# FPGA_Board_Input_Signals.net
KiCad netlist of a schematic drawn in Altium Designer
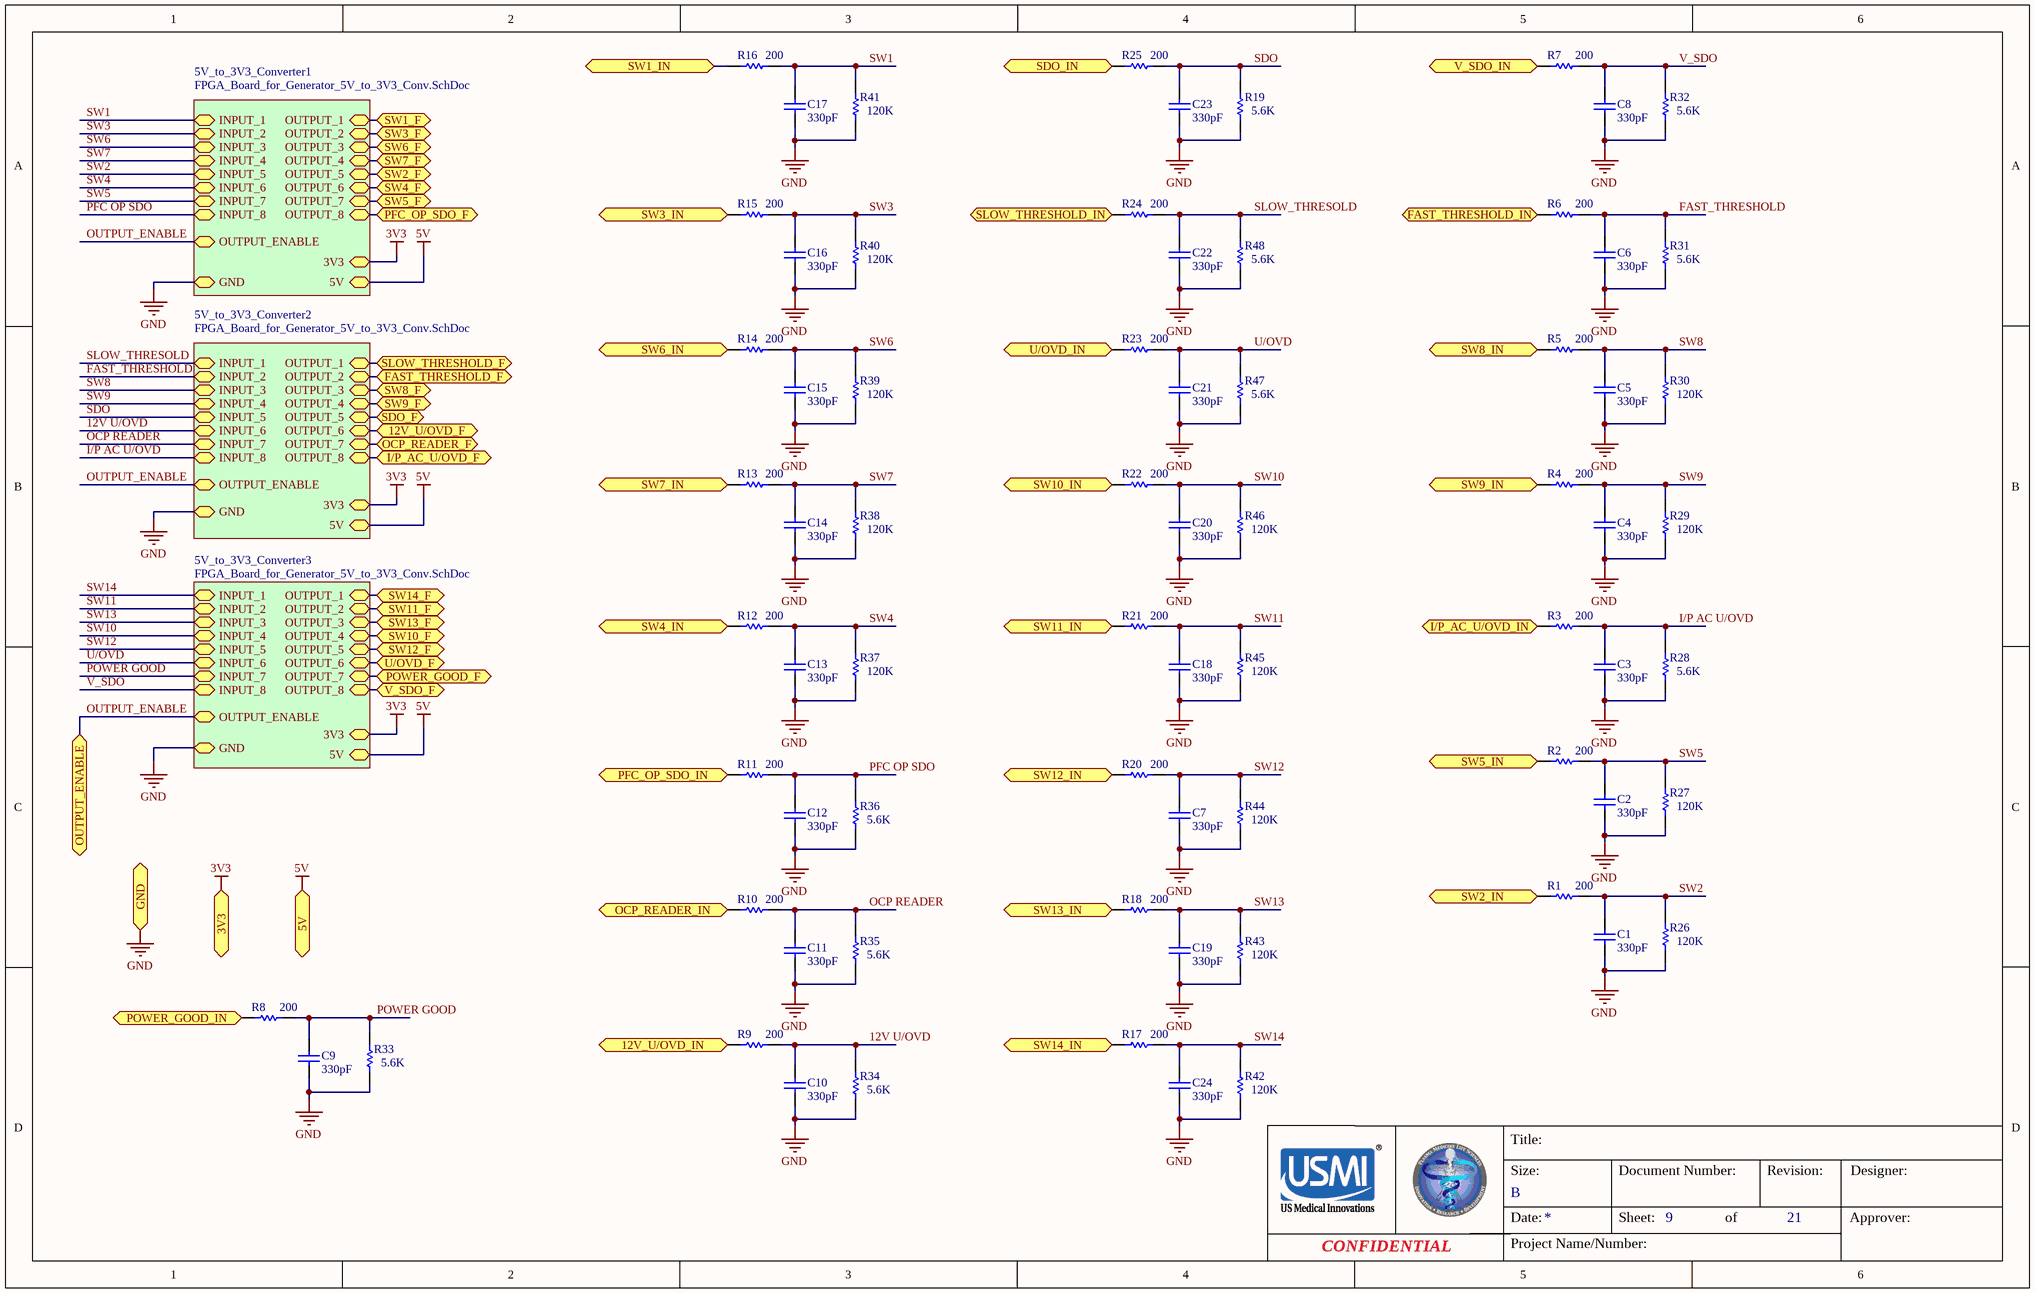
[diagram p0: FPGA_Board_Input_Signals.SchDoc]

(export (version "E")
  (design (tool "Eeschema 10.0.6"))
  (components
    (comp (ref "C1")
      (value "330pF")
      (footprint "0603c")
      (description "Capacitor")
      (fields (field (name "PUBLISHER") "Altium Limited"))
      (libsource (lib "Buddika Miscellaneous Devices") (part "Cap"))
    )
    (comp (ref "C2")
      (value "330pF")
      (footprint "0603c")
      (description "Capacitor")
      (fields (field (name "PUBLISHER") "Altium Limited"))
      (libsource (lib "Buddika Miscellaneous Devices") (part "Cap"))
    )
    (comp (ref "C3")
      (value "330pF")
      (footprint "0603c")
      (description "Capacitor")
      (fields (field (name "PUBLISHER") "Altium Limited"))
      (libsource (lib "Buddika Miscellaneous Devices") (part "Cap"))
    )
    (comp (ref "C4")
      (value "330pF")
      (footprint "0603c")
      (description "Capacitor")
      (fields (field (name "PUBLISHER") "Altium Limited"))
      (libsource (lib "Buddika Miscellaneous Devices") (part "Cap"))
    )
    (comp (ref "C5")
      (value "330pF")
      (footprint "0603c")
      (description "Capacitor")
      (fields (field (name "PUBLISHER") "Altium Limited"))
      (libsource (lib "Buddika Miscellaneous Devices") (part "Cap"))
    )
    (comp (ref "C6")
      (value "330pF")
      (footprint "0603c")
      (description "Capacitor")
      (fields (field (name "PUBLISHER") "Altium Limited"))
      (libsource (lib "Buddika Miscellaneous Devices") (part "Cap"))
    )
    (comp (ref "C7")
      (value "330pF")
      (footprint "0603c")
      (description "Capacitor")
      (fields (field (name "PUBLISHER") "Altium Limited"))
      (libsource (lib "Buddika Miscellaneous Devices") (part "Cap"))
    )
    (comp (ref "C8")
      (value "330pF")
      (footprint "0603c")
      (description "Capacitor")
      (fields (field (name "PUBLISHER") "Altium Limited"))
      (libsource (lib "Buddika Miscellaneous Devices") (part "Cap"))
    )
    (comp (ref "C9")
      (value "330pF")
      (footprint "0603c")
      (description "Capacitor")
      (fields (field (name "PUBLISHER") "Altium Limited"))
      (libsource (lib "Buddika Miscellaneous Devices") (part "Cap"))
    )
    (comp (ref "C10")
      (value "330pF")
      (footprint "0603c")
      (description "Capacitor")
      (fields (field (name "PUBLISHER") "Altium Limited"))
      (libsource (lib "Buddika Miscellaneous Devices") (part "Cap"))
    )
    (comp (ref "C11")
      (value "330pF")
      (footprint "0603c")
      (description "Capacitor")
      (fields (field (name "PUBLISHER") "Altium Limited"))
      (libsource (lib "Buddika Miscellaneous Devices") (part "Cap"))
    )
    (comp (ref "C12")
      (value "330pF")
      (footprint "0603c")
      (description "Capacitor")
      (fields (field (name "PUBLISHER") "Altium Limited"))
      (libsource (lib "Buddika Miscellaneous Devices") (part "Cap"))
    )
    (comp (ref "C13")
      (value "330pF")
      (footprint "0603c")
      (description "Capacitor")
      (fields (field (name "PUBLISHER") "Altium Limited"))
      (libsource (lib "Buddika Miscellaneous Devices") (part "Cap"))
    )
    (comp (ref "C14")
      (value "330pF")
      (footprint "0603c")
      (description "Capacitor")
      (fields (field (name "PUBLISHER") "Altium Limited"))
      (libsource (lib "Buddika Miscellaneous Devices") (part "Cap"))
    )
    (comp (ref "C15")
      (value "330pF")
      (footprint "0603c")
      (description "Capacitor")
      (fields (field (name "PUBLISHER") "Altium Limited"))
      (libsource (lib "Buddika Miscellaneous Devices") (part "Cap"))
    )
    (comp (ref "C16")
      (value "330pF")
      (footprint "0603c")
      (description "Capacitor")
      (fields (field (name "PUBLISHER") "Altium Limited"))
      (libsource (lib "Buddika Miscellaneous Devices") (part "Cap"))
    )
    (comp (ref "C17")
      (value "330pF")
      (footprint "0603c")
      (description "Capacitor")
      (fields (field (name "PUBLISHER") "Altium Limited"))
      (libsource (lib "Buddika Miscellaneous Devices") (part "Cap"))
    )
    (comp (ref "C18")
      (value "330pF")
      (footprint "0603c")
      (description "Capacitor")
      (fields (field (name "PUBLISHER") "Altium Limited"))
      (libsource (lib "Buddika Miscellaneous Devices") (part "Cap"))
    )
    (comp (ref "C19")
      (value "330pF")
      (footprint "0603c")
      (description "Capacitor")
      (fields (field (name "PUBLISHER") "Altium Limited"))
      (libsource (lib "Buddika Miscellaneous Devices") (part "Cap"))
    )
    (comp (ref "C20")
      (value "330pF")
      (footprint "0603c")
      (description "Capacitor")
      (fields (field (name "PUBLISHER") "Altium Limited"))
      (libsource (lib "Buddika Miscellaneous Devices") (part "Cap"))
    )
    (comp (ref "C21")
      (value "330pF")
      (footprint "0603c")
      (description "Capacitor")
      (fields (field (name "PUBLISHER") "Altium Limited"))
      (libsource (lib "Buddika Miscellaneous Devices") (part "Cap"))
    )
    (comp (ref "C22")
      (value "330pF")
      (footprint "0603c")
      (description "Capacitor")
      (fields (field (name "PUBLISHER") "Altium Limited"))
      (libsource (lib "Buddika Miscellaneous Devices") (part "Cap"))
    )
    (comp (ref "C23")
      (value "330pF")
      (footprint "0603c")
      (description "Capacitor")
      (fields (field (name "PUBLISHER") "Altium Limited"))
      (libsource (lib "Buddika Miscellaneous Devices") (part "Cap"))
    )
    (comp (ref "C24")
      (value "330pF")
      (footprint "0603c")
      (description "Capacitor")
      (fields (field (name "PUBLISHER") "Altium Limited"))
      (libsource (lib "Buddika Miscellaneous Devices") (part "Cap"))
    )
    (comp (ref "R1")
      (value "200")
      (footprint "0603R")
      (description "Resistor")
      (fields (field (name "PUBLISHER") "Altium Limited"))
      (libsource (lib "Buddika Miscellaneous Devices") (part "Res1"))
    )
    (comp (ref "R2")
      (value "200")
      (footprint "0603R")
      (description "Resistor")
      (fields (field (name "PUBLISHER") "Altium Limited"))
      (libsource (lib "Buddika Miscellaneous Devices") (part "Res1"))
    )
    (comp (ref "R3")
      (value "200")
      (footprint "0603R")
      (description "Resistor")
      (fields (field (name "PUBLISHER") "Altium Limited"))
      (libsource (lib "Buddika Miscellaneous Devices") (part "Res1"))
    )
    (comp (ref "R4")
      (value "200")
      (footprint "0603R")
      (description "Resistor")
      (fields (field (name "PUBLISHER") "Altium Limited"))
      (libsource (lib "Buddika Miscellaneous Devices") (part "Res1"))
    )
    (comp (ref "R5")
      (value "200")
      (footprint "0603R")
      (description "Resistor")
      (fields (field (name "PUBLISHER") "Altium Limited"))
      (libsource (lib "Buddika Miscellaneous Devices") (part "Res1"))
    )
    (comp (ref "R6")
      (value "200")
      (footprint "0603R")
      (description "Resistor")
      (fields (field (name "PUBLISHER") "Altium Limited"))
      (libsource (lib "Buddika Miscellaneous Devices") (part "Res1"))
    )
    (comp (ref "R7")
      (value "200")
      (footprint "0603R")
      (description "Resistor")
      (fields (field (name "PUBLISHER") "Altium Limited"))
      (libsource (lib "Buddika Miscellaneous Devices") (part "Res1"))
    )
    (comp (ref "R8")
      (value "200")
      (footprint "0603R")
      (description "Resistor")
      (fields (field (name "PUBLISHER") "Altium Limited"))
      (libsource (lib "Buddika Miscellaneous Devices") (part "Res1"))
    )
    (comp (ref "R9")
      (value "200")
      (footprint "0603R")
      (description "Resistor")
      (fields (field (name "PUBLISHER") "Altium Limited"))
      (libsource (lib "Buddika Miscellaneous Devices") (part "Res1"))
    )
    (comp (ref "R10")
      (value "200")
      (footprint "0603R")
      (description "Resistor")
      (fields (field (name "PUBLISHER") "Altium Limited"))
      (libsource (lib "Buddika Miscellaneous Devices") (part "Res1"))
    )
    (comp (ref "R11")
      (value "200")
      (footprint "0603R")
      (description "Resistor")
      (fields (field (name "PUBLISHER") "Altium Limited"))
      (libsource (lib "Buddika Miscellaneous Devices") (part "Res1"))
    )
    (comp (ref "R12")
      (value "200")
      (footprint "0603R")
      (description "Resistor")
      (fields (field (name "PUBLISHER") "Altium Limited"))
      (libsource (lib "Buddika Miscellaneous Devices") (part "Res1"))
    )
    (comp (ref "R13")
      (value "200")
      (footprint "0603R")
      (description "Resistor")
      (fields (field (name "PUBLISHER") "Altium Limited"))
      (libsource (lib "Buddika Miscellaneous Devices") (part "Res1"))
    )
    (comp (ref "R14")
      (value "200")
      (footprint "0603R")
      (description "Resistor")
      (fields (field (name "PUBLISHER") "Altium Limited"))
      (libsource (lib "Buddika Miscellaneous Devices") (part "Res1"))
    )
    (comp (ref "R15")
      (value "200")
      (footprint "0603R")
      (description "Resistor")
      (fields (field (name "PUBLISHER") "Altium Limited"))
      (libsource (lib "Buddika Miscellaneous Devices") (part "Res1"))
    )
    (comp (ref "R16")
      (value "200")
      (footprint "0603R")
      (description "Resistor")
      (fields (field (name "PUBLISHER") "Altium Limited"))
      (libsource (lib "Buddika Miscellaneous Devices") (part "Res1"))
    )
    (comp (ref "R17")
      (value "200")
      (footprint "0603R")
      (description "Resistor")
      (fields (field (name "PUBLISHER") "Altium Limited"))
      (libsource (lib "Buddika Miscellaneous Devices") (part "Res1"))
    )
    (comp (ref "R18")
      (value "200")
      (footprint "0603R")
      (description "Resistor")
      (fields (field (name "PUBLISHER") "Altium Limited"))
      (libsource (lib "Buddika Miscellaneous Devices") (part "Res1"))
    )
    (comp (ref "R19")
      (value "5.6K")
      (footprint "0603R")
      (description "Resistor")
      (fields (field (name "PUBLISHER") "Altium Limited"))
      (libsource (lib "Buddika Miscellaneous Devices") (part "Res1"))
    )
    (comp (ref "R20")
      (value "200")
      (footprint "0603R")
      (description "Resistor")
      (fields (field (name "PUBLISHER") "Altium Limited"))
      (libsource (lib "Buddika Miscellaneous Devices") (part "Res1"))
    )
    (comp (ref "R21")
      (value "200")
      (footprint "0603R")
      (description "Resistor")
      (fields (field (name "PUBLISHER") "Altium Limited"))
      (libsource (lib "Buddika Miscellaneous Devices") (part "Res1"))
    )
    (comp (ref "R22")
      (value "200")
      (footprint "0603R")
      (description "Resistor")
      (fields (field (name "PUBLISHER") "Altium Limited"))
      (libsource (lib "Buddika Miscellaneous Devices") (part "Res1"))
    )
    (comp (ref "R23")
      (value "200")
      (footprint "0603R")
      (description "Resistor")
      (fields (field (name "PUBLISHER") "Altium Limited"))
      (libsource (lib "Buddika Miscellaneous Devices") (part "Res1"))
    )
    (comp (ref "R24")
      (value "200")
      (footprint "0603R")
      (description "Resistor")
      (fields (field (name "PUBLISHER") "Altium Limited"))
      (libsource (lib "Buddika Miscellaneous Devices") (part "Res1"))
    )
    (comp (ref "R25")
      (value "200")
      (footprint "0603R")
      (description "Resistor")
      (fields (field (name "PUBLISHER") "Altium Limited"))
      (libsource (lib "Buddika Miscellaneous Devices") (part "Res1"))
    )
    (comp (ref "R26")
      (value "120K")
      (footprint "0603R")
      (description "Resistor")
      (fields (field (name "PUBLISHER") "Altium Limited"))
      (libsource (lib "Buddika Miscellaneous Devices") (part "Res1"))
    )
    (comp (ref "R27")
      (value "120K")
      (footprint "0603R")
      (description "Resistor")
      (fields (field (name "PUBLISHER") "Altium Limited"))
      (libsource (lib "Buddika Miscellaneous Devices") (part "Res1"))
    )
    (comp (ref "R28")
      (value "5.6K")
      (footprint "0603R")
      (description "Resistor")
      (fields (field (name "PUBLISHER") "Altium Limited"))
      (libsource (lib "Buddika Miscellaneous Devices") (part "Res1"))
    )
    (comp (ref "R29")
      (value "120K")
      (footprint "0603R")
      (description "Resistor")
      (fields (field (name "PUBLISHER") "Altium Limited"))
      (libsource (lib "Buddika Miscellaneous Devices") (part "Res1"))
    )
    (comp (ref "R30")
      (value "120K")
      (footprint "0603R")
      (description "Resistor")
      (fields (field (name "PUBLISHER") "Altium Limited"))
      (libsource (lib "Buddika Miscellaneous Devices") (part "Res1"))
    )
    (comp (ref "R31")
      (value "5.6K")
      (footprint "0603R")
      (description "Resistor")
      (fields (field (name "PUBLISHER") "Altium Limited"))
      (libsource (lib "Buddika Miscellaneous Devices") (part "Res1"))
    )
    (comp (ref "R32")
      (value "5.6K")
      (footprint "0603R")
      (description "Resistor")
      (fields (field (name "PUBLISHER") "Altium Limited"))
      (libsource (lib "Buddika Miscellaneous Devices") (part "Res1"))
    )
    (comp (ref "R33")
      (value "5.6K")
      (footprint "0603R")
      (description "Resistor")
      (fields (field (name "PUBLISHER") "Altium Limited"))
      (libsource (lib "Buddika Miscellaneous Devices") (part "Res1"))
    )
    (comp (ref "R34")
      (value "5.6K")
      (footprint "0603R")
      (description "Resistor")
      (fields (field (name "PUBLISHER") "Altium Limited"))
      (libsource (lib "Buddika Miscellaneous Devices") (part "Res1"))
    )
    (comp (ref "R35")
      (value "5.6K")
      (footprint "0603R")
      (description "Resistor")
      (fields (field (name "PUBLISHER") "Altium Limited"))
      (libsource (lib "Buddika Miscellaneous Devices") (part "Res1"))
    )
    (comp (ref "R36")
      (value "5.6K")
      (footprint "0603R")
      (description "Resistor")
      (fields (field (name "PUBLISHER") "Altium Limited"))
      (libsource (lib "Buddika Miscellaneous Devices") (part "Res1"))
    )
    (comp (ref "R37")
      (value "120K")
      (footprint "0603R")
      (description "Resistor")
      (fields (field (name "PUBLISHER") "Altium Limited"))
      (libsource (lib "Buddika Miscellaneous Devices") (part "Res1"))
    )
    (comp (ref "R38")
      (value "120K")
      (footprint "0603R")
      (description "Resistor")
      (fields (field (name "PUBLISHER") "Altium Limited"))
      (libsource (lib "Buddika Miscellaneous Devices") (part "Res1"))
    )
    (comp (ref "R39")
      (value "120K")
      (footprint "0603R")
      (description "Resistor")
      (fields (field (name "PUBLISHER") "Altium Limited"))
      (libsource (lib "Buddika Miscellaneous Devices") (part "Res1"))
    )
    (comp (ref "R40")
      (value "120K")
      (footprint "0603R")
      (description "Resistor")
      (fields (field (name "PUBLISHER") "Altium Limited"))
      (libsource (lib "Buddika Miscellaneous Devices") (part "Res1"))
    )
    (comp (ref "R41")
      (value "120K")
      (footprint "0603R")
      (description "Resistor")
      (fields (field (name "PUBLISHER") "Altium Limited"))
      (libsource (lib "Buddika Miscellaneous Devices") (part "Res1"))
    )
    (comp (ref "R42")
      (value "120K")
      (footprint "0603R")
      (description "Resistor")
      (fields (field (name "PUBLISHER") "Altium Limited"))
      (libsource (lib "Buddika Miscellaneous Devices") (part "Res1"))
    )
    (comp (ref "R43")
      (value "120K")
      (footprint "0603R")
      (description "Resistor")
      (fields (field (name "PUBLISHER") "Altium Limited"))
      (libsource (lib "Buddika Miscellaneous Devices") (part "Res1"))
    )
    (comp (ref "R44")
      (value "120K")
      (footprint "0603R")
      (description "Resistor")
      (fields (field (name "PUBLISHER") "Altium Limited"))
      (libsource (lib "Buddika Miscellaneous Devices") (part "Res1"))
    )
    (comp (ref "R45")
      (value "120K")
      (footprint "0603R")
      (description "Resistor")
      (fields (field (name "PUBLISHER") "Altium Limited"))
      (libsource (lib "Buddika Miscellaneous Devices") (part "Res1"))
    )
    (comp (ref "R46")
      (value "120K")
      (footprint "0603R")
      (description "Resistor")
      (fields (field (name "PUBLISHER") "Altium Limited"))
      (libsource (lib "Buddika Miscellaneous Devices") (part "Res1"))
    )
    (comp (ref "R47")
      (value "5.6K")
      (footprint "0603R")
      (description "Resistor")
      (fields (field (name "PUBLISHER") "Altium Limited"))
      (libsource (lib "Buddika Miscellaneous Devices") (part "Res1"))
    )
    (comp (ref "R48")
      (value "5.6K")
      (footprint "0603R")
      (description "Resistor")
      (fields (field (name "PUBLISHER") "Altium Limited"))
      (libsource (lib "Buddika Miscellaneous Devices") (part "Res1"))
    )
  )
  (nets
    (net (code "1") (name "/12V U{slash}OVD") (class "Default")
      (node (ref "C10") (pin "2") (pinfunction "2_2") (pintype "passive"))
      (node (ref "R34") (pin "2") (pinfunction "2_2") (pintype "passive"))
      (node (ref "R9") (pin "2") (pinfunction "2_2") (pintype "passive"))
    )
    (net (code "3") (name "/12V_U{slash}OVD_IN") (class "Default")
      (node (ref "R9") (pin "1") (pinfunction "1_1") (pintype "passive"))
    )
    (net (code "4") (name "/FAST_THRESHOLD") (class "Default")
      (node (ref "C6") (pin "2") (pinfunction "2_2") (pintype "passive"))
      (node (ref "R31") (pin "2") (pinfunction "2_2") (pintype "passive"))
      (node (ref "R6") (pin "2") (pinfunction "2_2") (pintype "passive"))
    )
    (net (code "6") (name "/FAST_THRESHOLD_IN") (class "Default")
      (node (ref "R6") (pin "1") (pinfunction "1_1") (pintype "passive"))
    )
    (net (code "7") (name "/I{slash}P AC U{slash}OVD") (class "Default")
      (node (ref "C3") (pin "2") (pinfunction "2_2") (pintype "passive"))
      (node (ref "R28") (pin "2") (pinfunction "2_2") (pintype "passive"))
      (node (ref "R3") (pin "2") (pinfunction "2_2") (pintype "passive"))
    )
    (net (code "9") (name "/I{slash}P_AC_U{slash}OVD_IN") (class "Default")
      (node (ref "R3") (pin "1") (pinfunction "1_1") (pintype "passive"))
    )
    (net (code "10") (name "/OCP READER") (class "Default")
      (node (ref "C11") (pin "2") (pinfunction "2_2") (pintype "passive"))
      (node (ref "R10") (pin "2") (pinfunction "2_2") (pintype "passive"))
      (node (ref "R35") (pin "2") (pinfunction "2_2") (pintype "passive"))
    )
    (net (code "12") (name "/OCP_READER_IN") (class "Default")
      (node (ref "R10") (pin "1") (pinfunction "1_1") (pintype "passive"))
    )
    (net (code "14") (name "/PFC OP SDO") (class "Default")
      (node (ref "C12") (pin "2") (pinfunction "2_2") (pintype "passive"))
      (node (ref "R11") (pin "2") (pinfunction "2_2") (pintype "passive"))
      (node (ref "R36") (pin "2") (pinfunction "2_2") (pintype "passive"))
    )
    (net (code "16") (name "/PFC_OP_SDO_IN") (class "Default")
      (node (ref "R11") (pin "1") (pinfunction "1_1") (pintype "passive"))
    )
    (net (code "17") (name "/POWER GOOD") (class "Default")
      (node (ref "C9") (pin "2") (pinfunction "2_2") (pintype "passive"))
      (node (ref "R33") (pin "2") (pinfunction "2_2") (pintype "passive"))
      (node (ref "R8") (pin "2") (pinfunction "2_2") (pintype "passive"))
    )
    (net (code "19") (name "/POWER_GOOD_IN") (class "Default")
      (node (ref "R8") (pin "1") (pinfunction "1_1") (pintype "passive"))
    )
    (net (code "20") (name "/SDO") (class "Default")
      (node (ref "C23") (pin "2") (pinfunction "2_2") (pintype "passive"))
      (node (ref "R19") (pin "2") (pinfunction "2_2") (pintype "passive"))
      (node (ref "R25") (pin "2") (pinfunction "2_2") (pintype "passive"))
    )
    (net (code "22") (name "/SDO_IN") (class "Default")
      (node (ref "R25") (pin "1") (pinfunction "1_1") (pintype "passive"))
    )
    (net (code "24") (name "/SLOW_THRESHOLD_IN") (class "Default")
      (node (ref "R24") (pin "1") (pinfunction "1_1") (pintype "passive"))
    )
    (net (code "25") (name "/SLOW_THRESOLD") (class "Default")
      (node (ref "C22") (pin "2") (pinfunction "2_2") (pintype "passive"))
      (node (ref "R24") (pin "2") (pinfunction "2_2") (pintype "passive"))
      (node (ref "R48") (pin "2") (pinfunction "2_2") (pintype "passive"))
    )
    (net (code "26") (name "/SW1") (class "Default")
      (node (ref "C17") (pin "2") (pinfunction "2_2") (pintype "passive"))
      (node (ref "R16") (pin "2") (pinfunction "2_2") (pintype "passive"))
      (node (ref "R41") (pin "2") (pinfunction "2_2") (pintype "passive"))
    )
    (net (code "28") (name "/SW1_IN") (class "Default")
      (node (ref "R16") (pin "1") (pinfunction "1_1") (pintype "passive"))
    )
    (net (code "29") (name "/SW2") (class "Default")
      (node (ref "C1") (pin "2") (pinfunction "2_2") (pintype "passive"))
      (node (ref "R1") (pin "2") (pinfunction "2_2") (pintype "passive"))
      (node (ref "R26") (pin "2") (pinfunction "2_2") (pintype "passive"))
    )
    (net (code "31") (name "/SW2_IN") (class "Default")
      (node (ref "R1") (pin "1") (pinfunction "1_1") (pintype "passive"))
    )
    (net (code "32") (name "/SW3") (class "Default")
      (node (ref "C16") (pin "2") (pinfunction "2_2") (pintype "passive"))
      (node (ref "R15") (pin "2") (pinfunction "2_2") (pintype "passive"))
      (node (ref "R40") (pin "2") (pinfunction "2_2") (pintype "passive"))
    )
    (net (code "34") (name "/SW3_IN") (class "Default")
      (node (ref "R15") (pin "1") (pinfunction "1_1") (pintype "passive"))
    )
    (net (code "35") (name "/SW4") (class "Default")
      (node (ref "C13") (pin "2") (pinfunction "2_2") (pintype "passive"))
      (node (ref "R12") (pin "2") (pinfunction "2_2") (pintype "passive"))
      (node (ref "R37") (pin "2") (pinfunction "2_2") (pintype "passive"))
    )
    (net (code "37") (name "/SW4_IN") (class "Default")
      (node (ref "R12") (pin "1") (pinfunction "1_1") (pintype "passive"))
    )
    (net (code "38") (name "/SW5") (class "Default")
      (node (ref "C2") (pin "2") (pinfunction "2_2") (pintype "passive"))
      (node (ref "R2") (pin "2") (pinfunction "2_2") (pintype "passive"))
      (node (ref "R27") (pin "2") (pinfunction "2_2") (pintype "passive"))
    )
    (net (code "40") (name "/SW5_IN") (class "Default")
      (node (ref "R2") (pin "1") (pinfunction "1_1") (pintype "passive"))
    )
    (net (code "41") (name "/SW6") (class "Default")
      (node (ref "C15") (pin "2") (pinfunction "2_2") (pintype "passive"))
      (node (ref "R14") (pin "2") (pinfunction "2_2") (pintype "passive"))
      (node (ref "R39") (pin "2") (pinfunction "2_2") (pintype "passive"))
    )
    (net (code "43") (name "/SW6_IN") (class "Default")
      (node (ref "R14") (pin "1") (pinfunction "1_1") (pintype "passive"))
    )
    (net (code "44") (name "/SW7") (class "Default")
      (node (ref "C14") (pin "2") (pinfunction "2_2") (pintype "passive"))
      (node (ref "R13") (pin "2") (pinfunction "2_2") (pintype "passive"))
      (node (ref "R38") (pin "2") (pinfunction "2_2") (pintype "passive"))
    )
    (net (code "46") (name "/SW7_IN") (class "Default")
      (node (ref "R13") (pin "1") (pinfunction "1_1") (pintype "passive"))
    )
    (net (code "47") (name "/SW8") (class "Default")
      (node (ref "C5") (pin "2") (pinfunction "2_2") (pintype "passive"))
      (node (ref "R30") (pin "2") (pinfunction "2_2") (pintype "passive"))
      (node (ref "R5") (pin "2") (pinfunction "2_2") (pintype "passive"))
    )
    (net (code "49") (name "/SW8_IN") (class "Default")
      (node (ref "R5") (pin "1") (pinfunction "1_1") (pintype "passive"))
    )
    (net (code "50") (name "/SW9") (class "Default")
      (node (ref "C4") (pin "2") (pinfunction "2_2") (pintype "passive"))
      (node (ref "R29") (pin "2") (pinfunction "2_2") (pintype "passive"))
      (node (ref "R4") (pin "2") (pinfunction "2_2") (pintype "passive"))
    )
    (net (code "52") (name "/SW9_IN") (class "Default")
      (node (ref "R4") (pin "1") (pinfunction "1_1") (pintype "passive"))
    )
    (net (code "53") (name "/SW10") (class "Default")
      (node (ref "C20") (pin "2") (pinfunction "2_2") (pintype "passive"))
      (node (ref "R22") (pin "2") (pinfunction "2_2") (pintype "passive"))
      (node (ref "R46") (pin "2") (pinfunction "2_2") (pintype "passive"))
    )
    (net (code "55") (name "/SW10_IN") (class "Default")
      (node (ref "R22") (pin "1") (pinfunction "1_1") (pintype "passive"))
    )
    (net (code "56") (name "/SW11") (class "Default")
      (node (ref "C18") (pin "2") (pinfunction "2_2") (pintype "passive"))
      (node (ref "R21") (pin "2") (pinfunction "2_2") (pintype "passive"))
      (node (ref "R45") (pin "2") (pinfunction "2_2") (pintype "passive"))
    )
    (net (code "58") (name "/SW11_IN") (class "Default")
      (node (ref "R21") (pin "1") (pinfunction "1_1") (pintype "passive"))
    )
    (net (code "59") (name "/SW12") (class "Default")
      (node (ref "C7") (pin "2") (pinfunction "2_2") (pintype "passive"))
      (node (ref "R20") (pin "2") (pinfunction "2_2") (pintype "passive"))
      (node (ref "R44") (pin "2") (pinfunction "2_2") (pintype "passive"))
    )
    (net (code "61") (name "/SW12_IN") (class "Default")
      (node (ref "R20") (pin "1") (pinfunction "1_1") (pintype "passive"))
    )
    (net (code "62") (name "/SW13") (class "Default")
      (node (ref "C19") (pin "2") (pinfunction "2_2") (pintype "passive"))
      (node (ref "R18") (pin "2") (pinfunction "2_2") (pintype "passive"))
      (node (ref "R43") (pin "2") (pinfunction "2_2") (pintype "passive"))
    )
    (net (code "64") (name "/SW13_IN") (class "Default")
      (node (ref "R18") (pin "1") (pinfunction "1_1") (pintype "passive"))
    )
    (net (code "65") (name "/SW14") (class "Default")
      (node (ref "C24") (pin "2") (pinfunction "2_2") (pintype "passive"))
      (node (ref "R17") (pin "2") (pinfunction "2_2") (pintype "passive"))
      (node (ref "R42") (pin "2") (pinfunction "2_2") (pintype "passive"))
    )
    (net (code "67") (name "/SW14_IN") (class "Default")
      (node (ref "R17") (pin "1") (pinfunction "1_1") (pintype "passive"))
    )
    (net (code "68") (name "/U{slash}OVD") (class "Default")
      (node (ref "C21") (pin "2") (pinfunction "2_2") (pintype "passive"))
      (node (ref "R23") (pin "2") (pinfunction "2_2") (pintype "passive"))
      (node (ref "R47") (pin "2") (pinfunction "2_2") (pintype "passive"))
    )
    (net (code "70") (name "/U{slash}OVD_IN") (class "Default")
      (node (ref "R23") (pin "1") (pinfunction "1_1") (pintype "passive"))
    )
    (net (code "71") (name "/V_SDO") (class "Default")
      (node (ref "C8") (pin "2") (pinfunction "2_2") (pintype "passive"))
      (node (ref "R32") (pin "2") (pinfunction "2_2") (pintype "passive"))
      (node (ref "R7") (pin "2") (pinfunction "2_2") (pintype "passive"))
    )
    (net (code "73") (name "/V_SDO_IN") (class "Default")
      (node (ref "R7") (pin "1") (pinfunction "1_1") (pintype "passive"))
    )
    (net (code "76") (name "GND") (class "Default")
      (node (ref "C1") (pin "1") (pinfunction "1_1") (pintype "passive"))
      (node (ref "C10") (pin "1") (pinfunction "1_1") (pintype "passive"))
      (node (ref "C11") (pin "1") (pinfunction "1_1") (pintype "passive"))
      (node (ref "C12") (pin "1") (pinfunction "1_1") (pintype "passive"))
      (node (ref "C13") (pin "1") (pinfunction "1_1") (pintype "passive"))
      (node (ref "C14") (pin "1") (pinfunction "1_1") (pintype "passive"))
      (node (ref "C15") (pin "1") (pinfunction "1_1") (pintype "passive"))
      (node (ref "C16") (pin "1") (pinfunction "1_1") (pintype "passive"))
      (node (ref "C17") (pin "1") (pinfunction "1_1") (pintype "passive"))
      (node (ref "C18") (pin "1") (pinfunction "1_1") (pintype "passive"))
      (node (ref "C19") (pin "1") (pinfunction "1_1") (pintype "passive"))
      (node (ref "C2") (pin "1") (pinfunction "1_1") (pintype "passive"))
      (node (ref "C20") (pin "1") (pinfunction "1_1") (pintype "passive"))
      (node (ref "C21") (pin "1") (pinfunction "1_1") (pintype "passive"))
      (node (ref "C22") (pin "1") (pinfunction "1_1") (pintype "passive"))
      (node (ref "C23") (pin "1") (pinfunction "1_1") (pintype "passive"))
      (node (ref "C24") (pin "1") (pinfunction "1_1") (pintype "passive"))
      (node (ref "C3") (pin "1") (pinfunction "1_1") (pintype "passive"))
      (node (ref "C4") (pin "1") (pinfunction "1_1") (pintype "passive"))
      (node (ref "C5") (pin "1") (pinfunction "1_1") (pintype "passive"))
      (node (ref "C6") (pin "1") (pinfunction "1_1") (pintype "passive"))
      (node (ref "C7") (pin "1") (pinfunction "1_1") (pintype "passive"))
      (node (ref "C8") (pin "1") (pinfunction "1_1") (pintype "passive"))
      (node (ref "C9") (pin "1") (pinfunction "1_1") (pintype "passive"))
      (node (ref "R19") (pin "1") (pinfunction "1_1") (pintype "passive"))
      (node (ref "R26") (pin "1") (pinfunction "1_1") (pintype "passive"))
      (node (ref "R27") (pin "1") (pinfunction "1_1") (pintype "passive"))
      (node (ref "R28") (pin "1") (pinfunction "1_1") (pintype "passive"))
      (node (ref "R29") (pin "1") (pinfunction "1_1") (pintype "passive"))
      (node (ref "R30") (pin "1") (pinfunction "1_1") (pintype "passive"))
      (node (ref "R31") (pin "1") (pinfunction "1_1") (pintype "passive"))
      (node (ref "R32") (pin "1") (pinfunction "1_1") (pintype "passive"))
      (node (ref "R33") (pin "1") (pinfunction "1_1") (pintype "passive"))
      (node (ref "R34") (pin "1") (pinfunction "1_1") (pintype "passive"))
      (node (ref "R35") (pin "1") (pinfunction "1_1") (pintype "passive"))
      (node (ref "R36") (pin "1") (pinfunction "1_1") (pintype "passive"))
      (node (ref "R37") (pin "1") (pinfunction "1_1") (pintype "passive"))
      (node (ref "R38") (pin "1") (pinfunction "1_1") (pintype "passive"))
      (node (ref "R39") (pin "1") (pinfunction "1_1") (pintype "passive"))
      (node (ref "R40") (pin "1") (pinfunction "1_1") (pintype "passive"))
      (node (ref "R41") (pin "1") (pinfunction "1_1") (pintype "passive"))
      (node (ref "R42") (pin "1") (pinfunction "1_1") (pintype "passive"))
      (node (ref "R43") (pin "1") (pinfunction "1_1") (pintype "passive"))
      (node (ref "R44") (pin "1") (pinfunction "1_1") (pintype "passive"))
      (node (ref "R45") (pin "1") (pinfunction "1_1") (pintype "passive"))
      (node (ref "R46") (pin "1") (pinfunction "1_1") (pintype "passive"))
      (node (ref "R47") (pin "1") (pinfunction "1_1") (pintype "passive"))
      (node (ref "R48") (pin "1") (pinfunction "1_1") (pintype "passive"))
    )
  )
)
